# LED_Driver_NF2L757GT-F1.net
KiCad netlist of a schematic drawn in Altium Designer
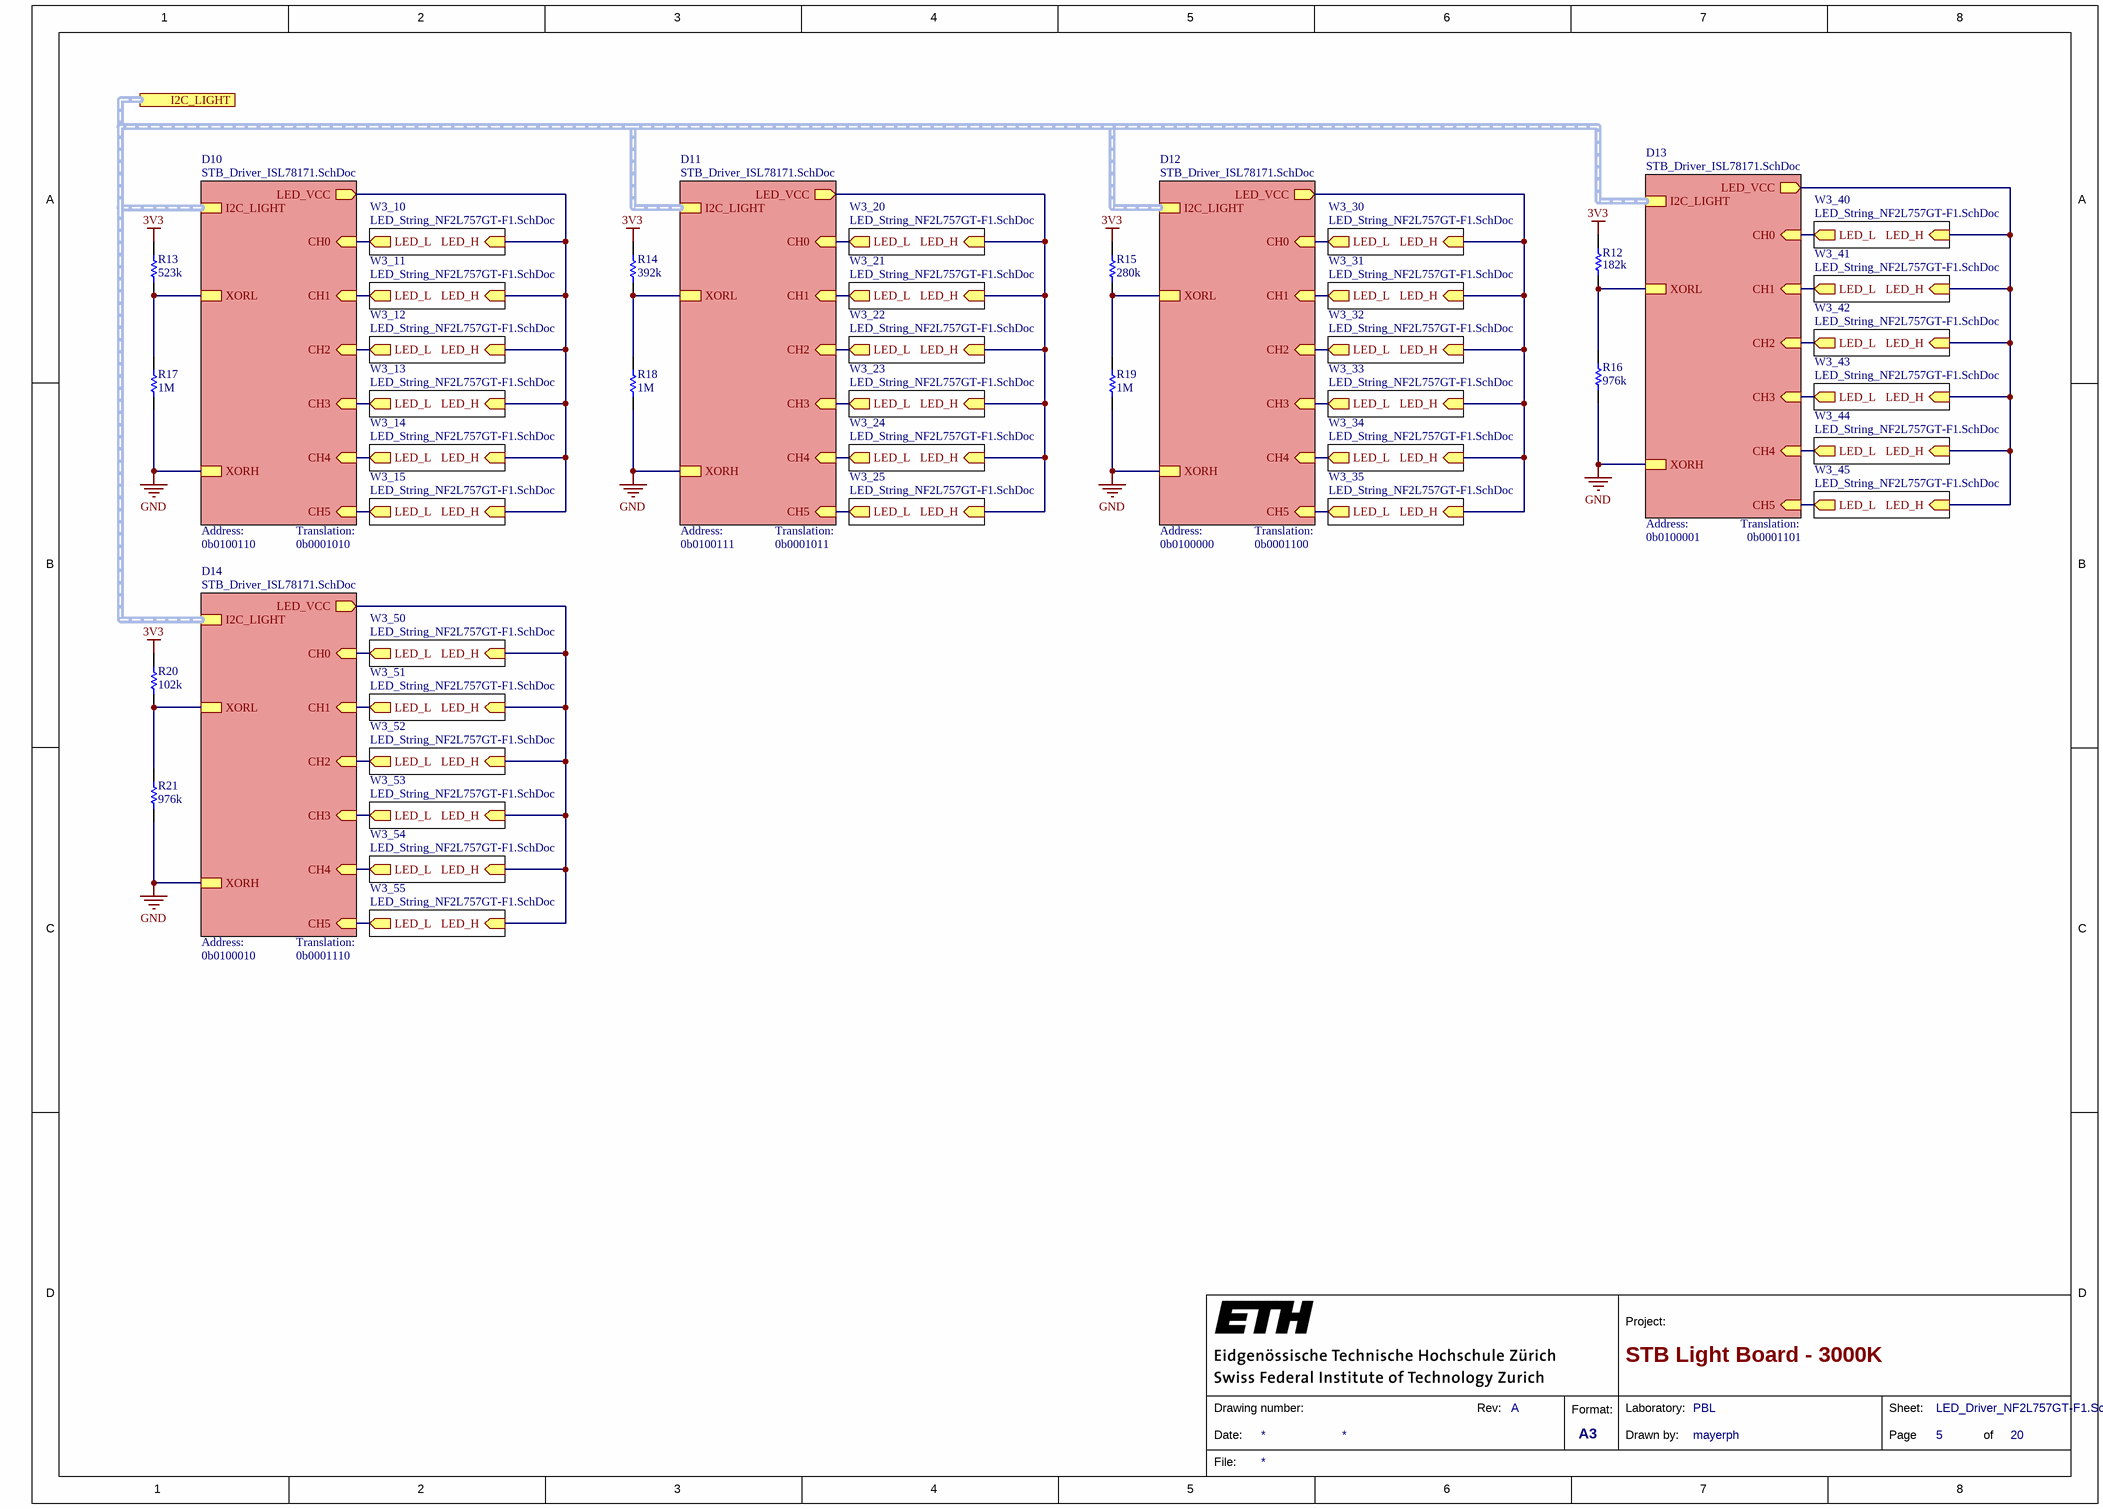
[diagram p0: LED_Driver_NF2L757GT-F1.SchDoc]

(export (version "E")
  (design (tool "Eeschema 10.0.6"))
  (components
    (comp (ref "R12")
      (value "182k")
      (footprint "RESC1005X40X25LL05T05")
      (fields
        (field (name "MANUFACTURER") "Vishay Dale")
        (field (name "PART NUMBER") "CRCW0402182KFKED")
        (field (name "TOLERANCE") "1%")
      )
      (libsource (lib "Altium Content Vault") (part "RES"))
    )
    (comp (ref "R13")
      (value "523k")
      (footprint "RESC1005X40X25LL05T05")
      (fields
        (field (name "MANUFACTURER") "Panasonic")
        (field (name "PART NUMBER") "ERJ-2RKF5233X")
        (field (name "TOLERANCE") "1%")
      )
      (libsource (lib "Altium Content Vault") (part "RES"))
    )
    (comp (ref "R14")
      (value "392k")
      (footprint "RESC1005X40X25LL05T05")
      (fields
        (field (name "PART NUMBER") "ERJ-2RKF3923X")
        (field (name "MANUFACTURER") "Panasonic")
        (field (name "TOLERANCE") "1%")
      )
      (libsource (lib "Altium Content Vault") (part "RES"))
    )
    (comp (ref "R15")
      (value "280k")
      (footprint "RESC1005X40X25LL05T05")
      (description "Chip Resistor, 280 KOhm, +/- 1%, 100 mW, -55 to 155 degC, 0402 (1005 Metric), RoHS, Cut Tape")
      (fields (field (name "PARTNUMBER") "ERJ-2RKF2803X") (field (name "MANUFACTURER") "Basic Passives"))
      (libsource (lib "Altium Content Vault") (part "RES-2"))
    )
    (comp (ref "R16")
      (value "976k")
      (footprint "RESC1005X40X25LL05T05")
      (fields
        (field (name "MANUFACTURER") "Panasonic")
        (field (name "PART NUMBER") "ERJ-2RKF9763X")
        (field (name "TOLERANCE") "1%")
      )
      (libsource (lib "Altium Content Vault") (part "RES"))
    )
    (comp (ref "R17")
      (value "1M")
      (footprint "RESC1005X40X25LL05T05")
      (description "Chip Resistor, 1 MOhm, +/- 1%, 100 mW, -55 to 155 degC, 0402 (1005 Metric), RoHS, Tape and Reel")
      (fields (field (name "PARTNUMBER") "ERJ-2RKF1004X") (field (name "TOLERANCE") "1%"))
      (libsource (lib "Altium Content Vault") (part "RES-2"))
    )
    (comp (ref "R18")
      (value "1M")
      (footprint "RESC1005X40X25LL05T05")
      (description "Chip Resistor, 1 MOhm, +/- 1%, 100 mW, -55 to 155 degC, 0402 (1005 Metric), RoHS, Tape and Reel")
      (fields (field (name "PARTNUMBER") "ERJ-2RKF1004X") (field (name "TOLERANCE") "1%"))
      (libsource (lib "Altium Content Vault") (part "RES-2"))
    )
    (comp (ref "R19")
      (value "1M")
      (footprint "RESC1005X40X25LL05T05")
      (description "Chip Resistor, 1 MOhm, +/- 1%, 100 mW, -55 to 155 degC, 0402 (1005 Metric), RoHS, Tape and Reel")
      (fields (field (name "PARTNUMBER") "ERJ-2RKF1004X") (field (name "TOLERANCE") "1%"))
      (libsource (lib "Altium Content Vault") (part "RES-2"))
    )
    (comp (ref "R20")
      (value "102k")
      (footprint "RESC1005X40X25LL05T05")
      (fields
        (field (name "MANUFACTURER") "Panasonic")
        (field (name "PART NUMBER") "ERJ-2RKF1023X")
        (field (name "TOLERANCE") "1%")
      )
      (libsource (lib "Altium Content Vault") (part "RES"))
    )
    (comp (ref "R21")
      (value "976k")
      (footprint "RESC1005X40X25LL05T05")
      (fields
        (field (name "MANUFACTURER") "Panasonic")
        (field (name "PART NUMBER") "ERJ-2RKF9763X")
        (field (name "TOLERANCE") "1%")
      )
      (libsource (lib "Altium Content Vault") (part "RES"))
    )
  )
  (nets
    (net (code "38") (name "/XORL") (class "Default")
      (node (ref "R12") (pin "1") (pinfunction "1_1") (pintype "passive"))
      (node (ref "R16") (pin "2") (pinfunction "2_2") (pintype "passive"))
    )
    (net (code "39") (name "/XORL_1") (class "Default")
      (node (ref "R20") (pin "1") (pinfunction "1_1") (pintype "passive"))
      (node (ref "R21") (pin "2") (pinfunction "2_2") (pintype "passive"))
    )
    (net (code "40") (name "/XORL_2") (class "Default")
      (node (ref "R13") (pin "1") (pinfunction "1_1") (pintype "passive"))
      (node (ref "R17") (pin "2") (pinfunction "2_2") (pintype "passive"))
    )
    (net (code "41") (name "/XORL_3") (class "Default")
      (node (ref "R14") (pin "1") (pinfunction "1_1") (pintype "passive"))
      (node (ref "R18") (pin "2") (pinfunction "2_2") (pintype "passive"))
    )
    (net (code "42") (name "/XORL_4") (class "Default")
      (node (ref "R15") (pin "1") (pinfunction "1_1") (pintype "passive"))
      (node (ref "R19") (pin "2") (pinfunction "2_2") (pintype "passive"))
    )
    (net (code "43") (name "3V3") (class "Default")
      (node (ref "R12") (pin "2") (pinfunction "2_2") (pintype "passive"))
      (node (ref "R13") (pin "2") (pinfunction "2_2") (pintype "passive"))
      (node (ref "R14") (pin "2") (pinfunction "2_2") (pintype "passive"))
      (node (ref "R15") (pin "2") (pinfunction "2_2") (pintype "passive"))
      (node (ref "R20") (pin "2") (pinfunction "2_2") (pintype "passive"))
    )
    (net (code "44") (name "GND") (class "Default")
      (node (ref "R16") (pin "1") (pinfunction "1_1") (pintype "passive"))
      (node (ref "R17") (pin "1") (pinfunction "1_1") (pintype "passive"))
      (node (ref "R18") (pin "1") (pinfunction "1_1") (pintype "passive"))
      (node (ref "R19") (pin "1") (pinfunction "1_1") (pintype "passive"))
      (node (ref "R21") (pin "1") (pinfunction "1_1") (pintype "passive"))
    )
  )
)
